# LC_FlowPCB_V6_3.net
KiCad netlist of a schematic drawn in Altium Designer
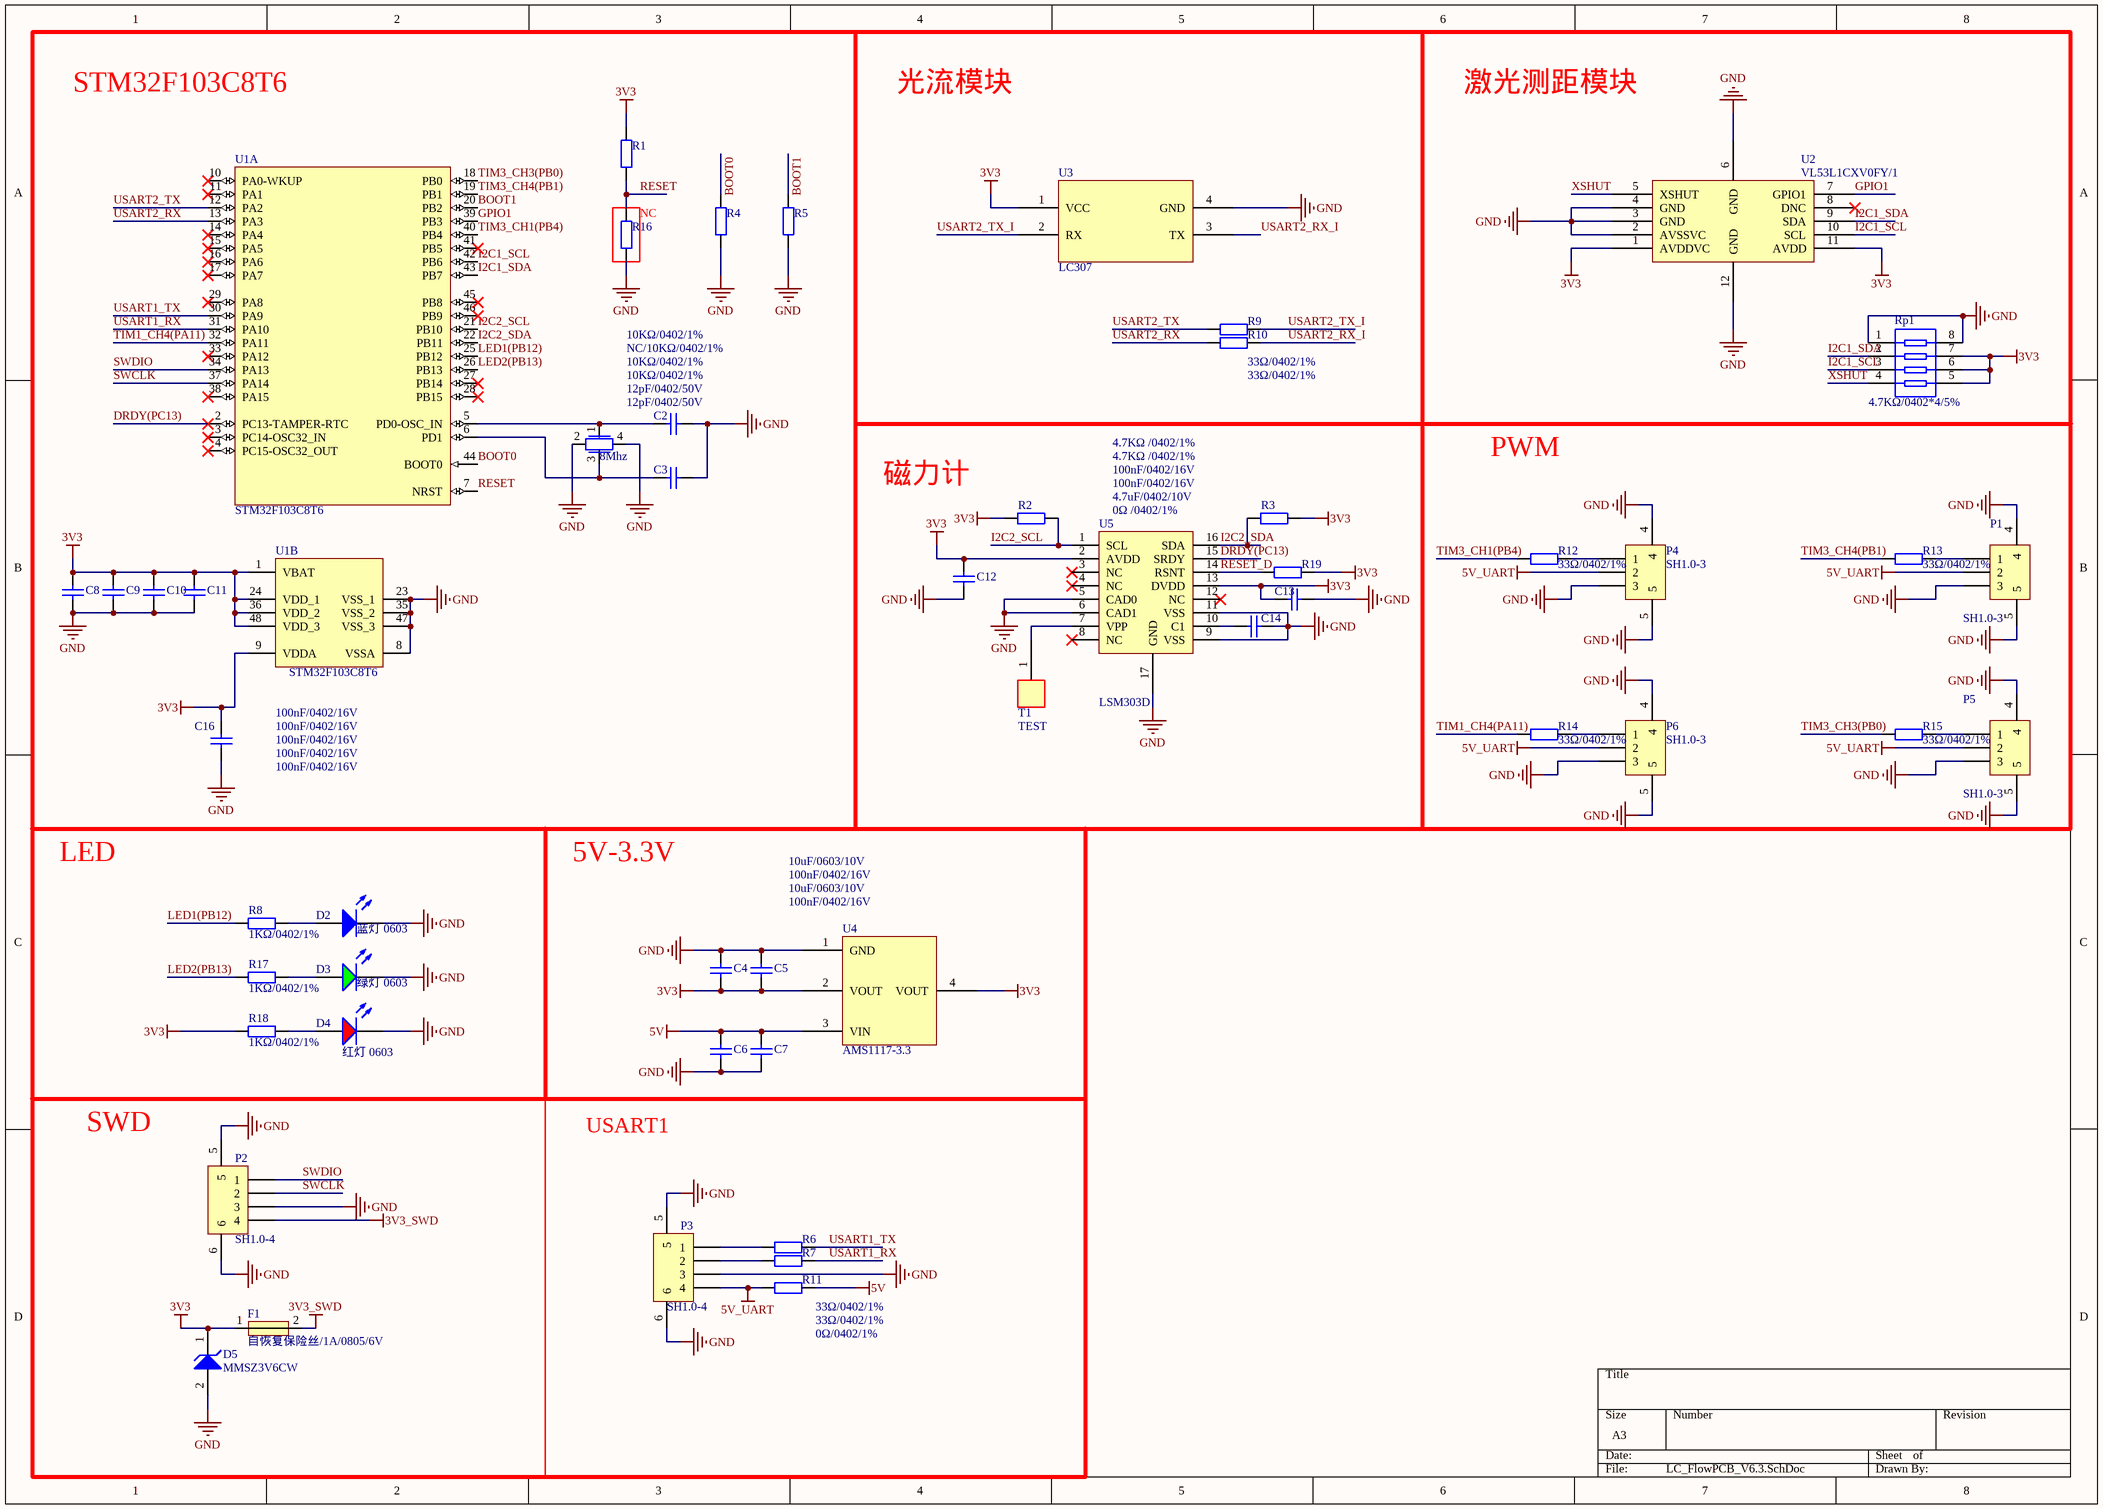
[diagram p0: LC_FlowPCB_V6.3.SchDoc]

(export (version "E")
  (design (tool "Eeschema 10.0.6"))
  (components
    (comp (ref "8Mhz")
      (value "无源贴片晶振")
      (footprint "RobotLab_Common_Used:SMD-3225_4P")
      (description "25M/3225")
      (libsource (lib "RobotLab_Common_Used") (part "XTAL_4"))
    )
    (comp (ref "C2")
      (value "12pF/0402/50V")
      (footprint "0402_C")
      (description "贴片电容")
      (libsource (lib "Miscellaneous Devices LC") (part "0402 22pF (220) 5% 50V"))
    )
    (comp (ref "C3")
      (value "12pF/0402/50V")
      (footprint "0402_C")
      (description "贴片电容")
      (libsource (lib "Miscellaneous Devices LC") (part "0402 22pF (220) 5% 50V"))
    )
    (comp (ref "C4")
      (value "10uF/0603/10V")
      (footprint "0603_C")
      (description "贴片电容")
      (libsource (lib "Miscellaneous Devices LC") (part "0603 10uF (106) 10% 10V"))
    )
    (comp (ref "C5")
      (value "100nF/0402/16V")
      (footprint "0402_C")
      (description "贴片电容")
      (libsource (lib "Miscellaneous Devices LC") (part "0402 100nF (104) 10% 16V"))
    )
    (comp (ref "C6")
      (value "10uF/0603/10V")
      (footprint "0603_C")
      (description "贴片电容")
      (libsource (lib "Miscellaneous Devices LC") (part "0603 10uF (106) 10% 10V"))
    )
    (comp (ref "C7")
      (value "100nF/0402/16V")
      (footprint "0402_C")
      (description "贴片电容")
      (libsource (lib "Miscellaneous Devices LC") (part "0402 100nF (104) 10% 16V"))
    )
    (comp (ref "C8")
      (value "100nF/0402/16V")
      (footprint "0402_C")
      (description "贴片电容")
      (libsource (lib "Miscellaneous Devices LC") (part "0402 100nF (104) 10% 16V"))
    )
    (comp (ref "C9")
      (value "100nF/0402/16V")
      (footprint "0402_C")
      (description "贴片电容")
      (libsource (lib "Miscellaneous Devices LC") (part "0402 100nF (104) 10% 16V"))
    )
    (comp (ref "C10")
      (value "100nF/0402/16V")
      (footprint "0402_C")
      (description "贴片电容")
      (libsource (lib "Miscellaneous Devices LC") (part "0402 100nF (104) 10% 16V"))
    )
    (comp (ref "C11")
      (value "100nF/0402/16V")
      (footprint "0402_C")
      (description "贴片电容")
      (libsource (lib "Miscellaneous Devices LC") (part "0402 100nF (104) 10% 16V"))
    )
    (comp (ref "C12")
      (value "100nF/0402/16V")
      (footprint "0402_C")
      (description "贴片电容")
      (libsource (lib "Miscellaneous Devices LC") (part "0402 100nF (104) 10% 16V"))
    )
    (comp (ref "C13")
      (value "100nF/0402/16V")
      (footprint "0402_C")
      (description "贴片电容")
      (libsource (lib "Miscellaneous Devices LC") (part "0402 100nF (104) 10% 16V"))
    )
    (comp (ref "C14")
      (value "4.7uF/0402/10V")
      (footprint "0402_C")
      (description "贴片电容")
      (libsource (lib "Miscellaneous Devices LC") (part "0402 4.7uF (475) 20% 10V"))
    )
    (comp (ref "C16")
      (value "100nF/0402/16V")
      (footprint "0402_C")
      (description "贴片电容")
      (libsource (lib "Miscellaneous Devices LC") (part "0402 100nF (104) 10% 16V"))
    )
    (comp (ref "D2")
      (value "蓝灯 0603")
      (footprint "0603_LED_S1")
      (description "发光二极管")
      (libsource (lib "Miscellaneous Devices LC") (part "0603 蓝灯"))
    )
    (comp (ref "D3")
      (value "绿灯 0603")
      (footprint "0603_LED_S1")
      (description "发光二极管")
      (libsource (lib "Miscellaneous Devices LC") (part "0603 绿灯"))
    )
    (comp (ref "D4")
      (value "红灯 0603")
      (footprint "0603_LED_S1")
      (description "发光二极管")
      (libsource (lib "Miscellaneous Devices LC") (part "0603 红灯"))
    )
    (comp (ref "D5")
      (value "MMSZ3V6CW")
      (footprint "SOD-123")
      (description "稳压二极管")
      (libsource (lib "LC_FlowPCB_V6.1") (part "LL-34 ZMM3V3"))
    )
    (comp (ref "F1")
      (value "自恢复保险丝/1A/0805/6V")
      (footprint "RobotLab_Common_Used:0805_R")
      (libsource (lib "RobotLab_Common_Used") (part "FUSE/0805"))
    )
    (comp (ref "P1")
      (value "SH1.0-3")
      (footprint "SH1.0-WS-3P")
      (description "Header, 3-Pin")
      (fields (field (name "PUBLISHER") "Altium Limited"))
      (libsource (lib "LC_FlowPCB_V6.1") (part "SH1.0-3"))
    )
    (comp (ref "P2")
      (value "SH1.0-4")
      (footprint "SH1.0-WS-4P")
      (description "Header, 4-Pin")
      (fields (field (name "PUBLISHER") "Altium Limited"))
      (libsource (lib "LC_FlowPCB_V6.1") (part "SH1.0-4"))
    )
    (comp (ref "P3")
      (value "SH1.0-4")
      (footprint "SH1.0-WS-4P")
      (description "Header, 4-Pin")
      (fields (field (name "PUBLISHER") "Altium Limited"))
      (libsource (lib "LC_FlowPCB_V6.1") (part "SH1.0-4"))
    )
    (comp (ref "P4")
      (value "SH1.0-3")
      (footprint "SH1.0-WS-3P")
      (description "Header, 3-Pin")
      (fields (field (name "PUBLISHER") "Altium Limited"))
      (libsource (lib "LC_FlowPCB_V6.1") (part "SH1.0-3"))
    )
    (comp (ref "P5")
      (value "SH1.0-3")
      (footprint "SH1.0-WS-3P")
      (description "Header, 3-Pin")
      (fields (field (name "PUBLISHER") "Altium Limited"))
      (libsource (lib "LC_FlowPCB_V6.1") (part "SH1.0-3"))
    )
    (comp (ref "P6")
      (value "SH1.0-3")
      (footprint "SH1.0-WS-3P")
      (description "Header, 3-Pin")
      (fields (field (name "PUBLISHER") "Altium Limited"))
      (libsource (lib "LC_FlowPCB_V6.1") (part "SH1.0-3"))
    )
    (comp (ref "R1")
      (value "10KΩ/0402/1%")
      (footprint "0402_R")
      (description "贴片电阻")
      (libsource (lib "Miscellaneous Devices LC") (part "0402 10KΩ (1002) 1%"))
    )
    (comp (ref "R2")
      (value "4.7KΩ /0402/1%")
      (footprint "0402_R")
      (description "贴片电阻")
      (libsource (lib "") (part "0402 4.7KΩ (4701) 1%_1"))
    )
    (comp (ref "R3")
      (value "4.7KΩ /0402/1%")
      (footprint "0402_R")
      (description "贴片电阻")
      (libsource (lib "Miscellaneous Devices LC") (part "0402 4.7KΩ (4701) 1%"))
    )
    (comp (ref "R4")
      (value "10KΩ/0402/1%")
      (footprint "0402_R")
      (description "贴片电阻")
      (libsource (lib "Miscellaneous Devices LC") (part "0402 10KΩ (1002) 1%"))
    )
    (comp (ref "R5")
      (value "10KΩ/0402/1%")
      (footprint "0402_R")
      (description "贴片电阻")
      (libsource (lib "Miscellaneous Devices LC") (part "0402 10KΩ (1002) 1%"))
    )
    (comp (ref "R6")
      (value "33Ω/0402/1%")
      (footprint "0402_R")
      (description "贴片电阻")
      (libsource (lib "") (part "0402 33Ω (33R0) 1%_1"))
    )
    (comp (ref "R7")
      (value "33Ω/0402/1%")
      (footprint "0402_R")
      (description "贴片电阻")
      (libsource (lib "") (part "0402 33Ω (33R0) 1%_1"))
    )
    (comp (ref "R8")
      (value "1KΩ/0402/1%")
      (footprint "0402_R")
      (description "贴片电阻")
      (libsource (lib "Miscellaneous Devices LC") (part "0402 1KΩ (1001) 1%"))
    )
    (comp (ref "R9")
      (value "33Ω/0402/1%")
      (footprint "0402_R")
      (description "贴片电阻")
      (libsource (lib "") (part "0402 33Ω (33R0) 1%_1"))
    )
    (comp (ref "R10")
      (value "33Ω/0402/1%")
      (footprint "0402_R")
      (description "贴片电阻")
      (libsource (lib "") (part "0402 33Ω (33R0) 1%_1"))
    )
    (comp (ref "R11")
      (value "0Ω/0402/1%")
      (footprint "0402_R")
      (description "贴片电阻")
      (libsource (lib "") (part "0402 33Ω (33R0) 1%_1"))
    )
    (comp (ref "R12")
      (value "33Ω/0402/1%")
      (footprint "0402_R")
      (description "贴片电阻")
      (libsource (lib "Miscellaneous Devices LC") (part "0402 33Ω (33R0) 1%"))
    )
    (comp (ref "R13")
      (value "33Ω/0402/1%")
      (footprint "0402_R")
      (description "贴片电阻")
      (libsource (lib "Miscellaneous Devices LC") (part "0402 33Ω (33R0) 1%"))
    )
    (comp (ref "R14")
      (value "33Ω/0402/1%")
      (footprint "0402_R")
      (description "贴片电阻")
      (libsource (lib "Miscellaneous Devices LC") (part "0402 33Ω (33R0) 1%"))
    )
    (comp (ref "R15")
      (value "33Ω/0402/1%")
      (footprint "0402_R")
      (description "贴片电阻")
      (libsource (lib "Miscellaneous Devices LC") (part "0402 33Ω (33R0) 1%"))
    )
    (comp (ref "R16")
      (value "NC/10KΩ/0402/1%")
      (footprint "0402_R")
      (description "贴片电阻")
      (libsource (lib "Miscellaneous Devices LC") (part "0402 10KΩ (1002) 1%"))
    )
    (comp (ref "R17")
      (value "1KΩ/0402/1%")
      (footprint "0402_R")
      (description "贴片电阻")
      (libsource (lib "Miscellaneous Devices LC") (part "0402 1KΩ (1001) 1%"))
    )
    (comp (ref "R18")
      (value "1KΩ/0402/1%")
      (footprint "0402_R")
      (description "贴片电阻")
      (libsource (lib "Miscellaneous Devices LC") (part "0402 1KΩ (1001) 1%"))
    )
    (comp (ref "R19")
      (value "0Ω /0402/1%")
      (footprint "0402_R")
      (description "贴片电阻")
      (libsource (lib "Miscellaneous Devices LC") (part "0402 4.7KΩ (4701) 1%"))
    )
    (comp (ref "Rp1")
      (value "4.7KΩ/0402*4/5%")
      (footprint "0402_Rx4")
      (description "贴片排阻")
      (libsource (lib "LC_FlowPCB_V6.1") (part "0402*4 1KΩ (102) 5%_1"))
    )
    (comp (ref "T1")
      (value "TEST")
      (footprint "测试点")
      (description "测试点")
      (libsource (lib "LC_FlowPCB_V6.1") (part "测试点"))
    )
    (comp (ref "U1")
      (value "STM32F103C8T6")
      (footprint "LQFP-48_7x7x05P")
      (description "ARM")
      (libsource (lib "Miscellaneous Devices LC") (part "STM32F103C8T6"))
    )
    (comp (ref "U2")
      (value "VL53L1CXV0FY/1")
      (footprint "LGA-12-2.5X4.9MM")
      (description "激光测距模块")
      (libsource (lib "LC_FlowPCB_V6.1") (part "VL53L1CXV0FY/1"))
    )
    (comp (ref "U3")
      (value "LC307")
      (footprint "LC307")
      (description "光流模块")
      (libsource (lib "LC_FlowPCB_V6.1") (part "LC307"))
    )
    (comp (ref "U4")
      (value "AMS1117-3.3")
      (footprint "SOT223")
      (description "LDO")
      (libsource (lib "LC_FlowPCB_V6.1") (part "AMS1117-3.3"))
    )
    (comp (ref "U5")
      (value "LSM303D")
      (footprint "QFN-16 (3×3)")
      (description "磁力计")
      (libsource (lib "LC_FlowPCB_V6.1") (part "IST8310"))
    )
  )
  (nets
    (net (code "1") (name "/BOOT0") (class "Default")
      (node (ref "R4") (pin "2") (pinfunction "2_2") (pintype "passive"))
      (node (ref "U1") (pin "44") (pinfunction "BOOT0_44") (pintype "input"))
    )
    (net (code "2") (name "/BOOT1") (class "Default")
      (node (ref "R5") (pin "2") (pinfunction "2_2") (pintype "passive"))
      (node (ref "U1") (pin "20") (pinfunction "PB2_20") (pintype "bidirectional"))
    )
    (net (code "3") (name "/DRDY(PC13)") (class "Default")
      (node (ref "U1") (pin "2") (pinfunction "PC13-TAMPER-RTC_2") (pintype "bidirectional"))
      (node (ref "U5") (pin "15") (pinfunction "SRDY_15") (pintype "passive"))
    )
    (net (code "4") (name "/GPIO1") (class "Default")
      (node (ref "U1") (pin "39") (pinfunction "PB3_39") (pintype "bidirectional"))
      (node (ref "U2") (pin "7") (pinfunction "GPIO1_7") (pintype "passive"))
    )
    (net (code "5") (name "/I2C1_SCL") (class "Default")
      (node (ref "Rp1") (pin "3") (pinfunction "3_3") (pintype "passive"))
      (node (ref "U1") (pin "42") (pinfunction "PB6_42") (pintype "bidirectional"))
      (node (ref "U2") (pin "10") (pinfunction "SCL_10") (pintype "passive"))
    )
    (net (code "6") (name "/I2C1_SDA") (class "Default")
      (node (ref "Rp1") (pin "2") (pinfunction "2_2") (pintype "passive"))
      (node (ref "U1") (pin "43") (pinfunction "PB7_43") (pintype "bidirectional"))
      (node (ref "U2") (pin "9") (pinfunction "SDA_9") (pintype "passive"))
    )
    (net (code "7") (name "/I2C2_SCL") (class "Default")
      (node (ref "R2") (pin "1") (pinfunction "1_1") (pintype "passive"))
      (node (ref "U1") (pin "21") (pinfunction "PB10_21") (pintype "bidirectional"))
      (node (ref "U5") (pin "1") (pinfunction "SCL_1") (pintype "passive"))
    )
    (net (code "8") (name "/I2C2_SDA") (class "Default")
      (node (ref "R3") (pin "1") (pinfunction "1_1") (pintype "passive"))
      (node (ref "U1") (pin "22") (pinfunction "PB11_22") (pintype "bidirectional"))
      (node (ref "U5") (pin "16") (pinfunction "SDA_16") (pintype "passive"))
    )
    (net (code "9") (name "/LED1(PB12)") (class "Default")
      (node (ref "R8") (pin "1") (pinfunction "1_1") (pintype "passive"))
      (node (ref "U1") (pin "25") (pinfunction "PB12_25") (pintype "bidirectional"))
    )
    (net (code "10") (name "/LED2(PB13)") (class "Default")
      (node (ref "R17") (pin "1") (pinfunction "1_1") (pintype "passive"))
      (node (ref "U1") (pin "26") (pinfunction "PB13_26") (pintype "bidirectional"))
    )
    (net (code "11") (name "/RESET") (class "Default")
      (node (ref "R1") (pin "1") (pinfunction "1_1") (pintype "passive"))
      (node (ref "R16") (pin "2") (pinfunction "2_2") (pintype "passive"))
      (node (ref "U1") (pin "7") (pinfunction "NRST_7") (pintype "bidirectional"))
    )
    (net (code "12") (name "/RESET_D") (class "Default")
      (node (ref "R19") (pin "1") (pinfunction "1_1") (pintype "passive"))
      (node (ref "U5") (pin "14") (pinfunction "RSNT_14") (pintype "passive"))
    )
    (net (code "13") (name "/SWCLK") (class "Default")
      (node (ref "P2") (pin "2") (pinfunction "2_2") (pintype "passive"))
      (node (ref "U1") (pin "37") (pinfunction "PA14_37") (pintype "bidirectional"))
    )
    (net (code "14") (name "/SWDIO") (class "Default")
      (node (ref "P2") (pin "1") (pinfunction "1_1") (pintype "passive"))
      (node (ref "U1") (pin "34") (pinfunction "PA13_34") (pintype "bidirectional"))
    )
    (net (code "15") (name "/TIM1_CH4(PA11)") (class "Default")
      (node (ref "R14") (pin "2") (pinfunction "2_2") (pintype "passive"))
      (node (ref "U1") (pin "32") (pinfunction "PA11_32") (pintype "bidirectional"))
    )
    (net (code "16") (name "/TIM3_CH1(PB4)") (class "Default")
      (node (ref "R12") (pin "2") (pinfunction "2_2") (pintype "passive"))
      (node (ref "U1") (pin "40") (pinfunction "PB4_40") (pintype "bidirectional"))
    )
    (net (code "17") (name "/TIM3_CH3(PB0)") (class "Default")
      (node (ref "R15") (pin "2") (pinfunction "2_2") (pintype "passive"))
      (node (ref "U1") (pin "18") (pinfunction "PB0_18") (pintype "bidirectional"))
    )
    (net (code "18") (name "/TIM3_CH4(PB1)") (class "Default")
      (node (ref "R13") (pin "2") (pinfunction "2_2") (pintype "passive"))
      (node (ref "U1") (pin "19") (pinfunction "PB1_19") (pintype "bidirectional"))
    )
    (net (code "19") (name "/USART1_RX") (class "Default")
      (node (ref "R7") (pin "2") (pinfunction "2_2") (pintype "passive"))
      (node (ref "U1") (pin "31") (pinfunction "PA10_31") (pintype "bidirectional"))
    )
    (net (code "20") (name "/USART1_TX") (class "Default")
      (node (ref "R6") (pin "2") (pinfunction "2_2") (pintype "passive"))
      (node (ref "U1") (pin "30") (pinfunction "PA9_30") (pintype "bidirectional"))
    )
    (net (code "21") (name "/USART2_RX") (class "Default")
      (node (ref "R10") (pin "1") (pinfunction "1_1") (pintype "passive"))
      (node (ref "U1") (pin "13") (pinfunction "PA3_13") (pintype "bidirectional"))
    )
    (net (code "22") (name "/USART2_RX_I") (class "Default")
      (node (ref "R10") (pin "2") (pinfunction "2_2") (pintype "passive"))
      (node (ref "U3") (pin "3") (pinfunction "TX_3") (pintype "passive"))
    )
    (net (code "23") (name "/USART2_TX") (class "Default")
      (node (ref "R9") (pin "1") (pinfunction "1_1") (pintype "passive"))
      (node (ref "U1") (pin "12") (pinfunction "PA2_12") (pintype "bidirectional"))
    )
    (net (code "24") (name "/USART2_TX_I") (class "Default")
      (node (ref "R9") (pin "2") (pinfunction "2_2") (pintype "passive"))
      (node (ref "U3") (pin "2") (pinfunction "RX_2") (pintype "passive"))
    )
    (net (code "25") (name "/XSHUT") (class "Default")
      (node (ref "Rp1") (pin "4") (pinfunction "4_4") (pintype "passive"))
      (node (ref "U2") (pin "5") (pinfunction "XSHUT_5") (pintype "passive"))
    )
    (net (code "26") (name "3V3") (class "Default")
      (node (ref "C10") (pin "2") (pinfunction "2_2") (pintype "passive"))
      (node (ref "C11") (pin "2") (pinfunction "2_2") (pintype "passive"))
      (node (ref "C12") (pin "2") (pinfunction "2_2") (pintype "passive"))
      (node (ref "C13") (pin "2") (pinfunction "2_2") (pintype "passive"))
      (node (ref "C16") (pin "2") (pinfunction "2_2") (pintype "passive"))
      (node (ref "C4") (pin "1") (pinfunction "1_1") (pintype "passive"))
      (node (ref "C5") (pin "1") (pinfunction "1_1") (pintype "passive"))
      (node (ref "C8") (pin "2") (pinfunction "2_2") (pintype "passive"))
      (node (ref "C9") (pin "2") (pinfunction "2_2") (pintype "passive"))
      (node (ref "D5") (pin "1") (pinfunction "K_1") (pintype "passive"))
      (node (ref "F1") (pin "1") (pintype "passive"))
      (node (ref "R1") (pin "2") (pinfunction "2_2") (pintype "passive"))
      (node (ref "R18") (pin "1") (pinfunction "1_1") (pintype "passive"))
      (node (ref "R19") (pin "2") (pinfunction "2_2") (pintype "passive"))
      (node (ref "R2") (pin "2") (pinfunction "2_2") (pintype "passive"))
      (node (ref "R3") (pin "2") (pinfunction "2_2") (pintype "passive"))
      (node (ref "Rp1") (pin "5") (pinfunction "5_5") (pintype "passive"))
      (node (ref "Rp1") (pin "6") (pinfunction "6_6") (pintype "passive"))
      (node (ref "Rp1") (pin "7") (pinfunction "7_7") (pintype "passive"))
      (node (ref "U1") (pin "1") (pinfunction "VBAT_1") (pintype "power_in"))
      (node (ref "U1") (pin "24") (pinfunction "VDD_1_24") (pintype "power_in"))
      (node (ref "U1") (pin "36") (pinfunction "VDD_2_36") (pintype "power_in"))
      (node (ref "U1") (pin "48") (pinfunction "VDD_3_48") (pintype "power_in"))
      (node (ref "U1") (pin "9") (pinfunction "VDDA_9") (pintype "power_in"))
      (node (ref "U2") (pin "1") (pinfunction "AVDDVC_1") (pintype "passive"))
      (node (ref "U2") (pin "11") (pinfunction "AVDD_11") (pintype "passive"))
      (node (ref "U3") (pin "1") (pinfunction "VCC_1") (pintype "passive"))
      (node (ref "U4") (pin "2") (pinfunction "VOUT_2") (pintype "passive"))
      (node (ref "U4") (pin "4") (pinfunction "VOUT_4") (pintype "passive"))
      (node (ref "U5") (pin "13") (pinfunction "DVDD_13") (pintype "passive"))
      (node (ref "U5") (pin "2") (pinfunction "AVDD_2") (pintype "passive"))
    )
    (net (code "27") (name "3V3_SWD") (class "Default")
      (node (ref "F1") (pin "2") (pintype "passive"))
      (node (ref "P2") (pin "4") (pinfunction "4_4") (pintype "passive"))
    )
    (net (code "28") (name "5V") (class "Default")
      (node (ref "C6") (pin "2") (pinfunction "2_2") (pintype "passive"))
      (node (ref "C7") (pin "2") (pinfunction "2_2") (pintype "passive"))
      (node (ref "R11") (pin "2") (pinfunction "2_2") (pintype "passive"))
      (node (ref "U4") (pin "3") (pinfunction "VIN_3") (pintype "passive"))
    )
    (net (code "29") (name "5V_UART") (class "Default")
      (node (ref "P1") (pin "2") (pinfunction "2_2") (pintype "passive"))
      (node (ref "P3") (pin "4") (pinfunction "4_4") (pintype "passive"))
      (node (ref "P4") (pin "2") (pinfunction "2_2") (pintype "passive"))
      (node (ref "P5") (pin "2") (pinfunction "2_2") (pintype "passive"))
      (node (ref "P6") (pin "2") (pinfunction "2_2") (pintype "passive"))
      (node (ref "R11") (pin "1") (pinfunction "1_1") (pintype "passive"))
    )
    (net (code "30") (name "GND") (class "Default")
      (node (ref "8Mhz") (pin "2") (pinfunction "GND_2") (pintype "passive"))
      (node (ref "8Mhz") (pin "4") (pinfunction "GND_4") (pintype "passive"))
      (node (ref "C10") (pin "1") (pinfunction "1_1") (pintype "passive"))
      (node (ref "C11") (pin "1") (pinfunction "1_1") (pintype "passive"))
      (node (ref "C12") (pin "1") (pinfunction "1_1") (pintype "passive"))
      (node (ref "C13") (pin "1") (pinfunction "1_1") (pintype "passive"))
      (node (ref "C14") (pin "2") (pinfunction "2_2") (pintype "passive"))
      (node (ref "C16") (pin "1") (pinfunction "1_1") (pintype "passive"))
      (node (ref "C2") (pin "2") (pinfunction "2_2") (pintype "passive"))
      (node (ref "C3") (pin "2") (pinfunction "2_2") (pintype "passive"))
      (node (ref "C4") (pin "2") (pinfunction "2_2") (pintype "passive"))
      (node (ref "C5") (pin "2") (pinfunction "2_2") (pintype "passive"))
      (node (ref "C6") (pin "1") (pinfunction "1_1") (pintype "passive"))
      (node (ref "C7") (pin "1") (pinfunction "1_1") (pintype "passive"))
      (node (ref "C8") (pin "1") (pinfunction "1_1") (pintype "passive"))
      (node (ref "C9") (pin "1") (pinfunction "1_1") (pintype "passive"))
      (node (ref "D2") (pin "K") (pinfunction "K_K") (pintype "passive"))
      (node (ref "D3") (pin "K") (pinfunction "K_K") (pintype "passive"))
      (node (ref "D4") (pin "K") (pinfunction "K_K") (pintype "passive"))
      (node (ref "D5") (pin "2") (pinfunction "A_2") (pintype "passive"))
      (node (ref "P1") (pin "3") (pinfunction "3_3") (pintype "passive"))
      (node (ref "P1") (pin "4") (pinfunction "4_4") (pintype "passive"))
      (node (ref "P1") (pin "5") (pinfunction "5_5") (pintype "passive"))
      (node (ref "P2") (pin "3") (pinfunction "3_3") (pintype "passive"))
      (node (ref "P2") (pin "5") (pinfunction "5_5") (pintype "passive"))
      (node (ref "P2") (pin "6") (pinfunction "6_6") (pintype "passive"))
      (node (ref "P3") (pin "3") (pinfunction "3_3") (pintype "passive"))
      (node (ref "P3") (pin "5") (pinfunction "5_5") (pintype "passive"))
      (node (ref "P3") (pin "6") (pinfunction "6_6") (pintype "passive"))
      (node (ref "P4") (pin "3") (pinfunction "3_3") (pintype "passive"))
      (node (ref "P4") (pin "4") (pinfunction "4_4") (pintype "passive"))
      (node (ref "P4") (pin "5") (pinfunction "5_5") (pintype "passive"))
      (node (ref "P5") (pin "3") (pinfunction "3_3") (pintype "passive"))
      (node (ref "P5") (pin "4") (pinfunction "4_4") (pintype "passive"))
      (node (ref "P5") (pin "5") (pinfunction "5_5") (pintype "passive"))
      (node (ref "P6") (pin "3") (pinfunction "3_3") (pintype "passive"))
      (node (ref "P6") (pin "4") (pinfunction "4_4") (pintype "passive"))
      (node (ref "P6") (pin "5") (pinfunction "5_5") (pintype "passive"))
      (node (ref "R16") (pin "1") (pinfunction "1_1") (pintype "passive"))
      (node (ref "R4") (pin "1") (pinfunction "1_1") (pintype "passive"))
      (node (ref "R5") (pin "1") (pinfunction "1_1") (pintype "passive"))
      (node (ref "Rp1") (pin "1") (pinfunction "1_1") (pintype "passive"))
      (node (ref "Rp1") (pin "8") (pinfunction "8_8") (pintype "passive"))
      (node (ref "U1") (pin "23") (pinfunction "VSS_1_23") (pintype "power_in"))
      (node (ref "U1") (pin "35") (pinfunction "VSS_2_35") (pintype "power_in"))
      (node (ref "U1") (pin "47") (pinfunction "VSS_3_47") (pintype "power_in"))
      (node (ref "U1") (pin "8") (pinfunction "VSSA_8") (pintype "power_in"))
      (node (ref "U2") (pin "12") (pinfunction "GND_12") (pintype "passive"))
      (node (ref "U2") (pin "2") (pinfunction "AVSSVC_2") (pintype "passive"))
      (node (ref "U2") (pin "3") (pinfunction "GND_3") (pintype "passive"))
      (node (ref "U2") (pin "4") (pinfunction "GND_4") (pintype "passive"))
      (node (ref "U2") (pin "6") (pinfunction "GND_6") (pintype "passive"))
      (node (ref "U3") (pin "4") (pinfunction "GND_4") (pintype "passive"))
      (node (ref "U4") (pin "1") (pinfunction "GND_1") (pintype "passive"))
      (node (ref "U5") (pin "11") (pinfunction "VSS_11") (pintype "passive"))
      (node (ref "U5") (pin "17") (pinfunction "GND_17") (pintype "passive"))
      (node (ref "U5") (pin "5") (pinfunction "CAD0_5") (pintype "passive"))
      (node (ref "U5") (pin "6") (pinfunction "CAD1_6") (pintype "passive"))
      (node (ref "U5") (pin "9") (pinfunction "VSS_9") (pintype "passive"))
    )
    (net (code "31") (name "Net-(D2-PadA)") (class "Default")
      (node (ref "D2") (pin "A") (pinfunction "A_A") (pintype "passive"))
      (node (ref "R8") (pin "2") (pinfunction "2_2") (pintype "passive"))
    )
    (net (code "32") (name "Net-(D3-PadA)") (class "Default")
      (node (ref "D3") (pin "A") (pinfunction "A_A") (pintype "passive"))
      (node (ref "R17") (pin "2") (pinfunction "2_2") (pintype "passive"))
    )
    (net (code "33") (name "Net-(D4-PadA)") (class "Default")
      (node (ref "D4") (pin "A") (pinfunction "A_A") (pintype "passive"))
      (node (ref "R18") (pin "2") (pinfunction "2_2") (pintype "passive"))
    )
    (net (code "34") (name "Net-(P1-Pad1)") (class "Default")
      (node (ref "P1") (pin "1") (pinfunction "1_1") (pintype "passive"))
      (node (ref "R13") (pin "1") (pinfunction "1_1") (pintype "passive"))
    )
    (net (code "35") (name "Net-(P3-Pad1)") (class "Default")
      (node (ref "P3") (pin "1") (pinfunction "1_1") (pintype "passive"))
      (node (ref "R6") (pin "1") (pinfunction "1_1") (pintype "passive"))
    )
    (net (code "36") (name "Net-(P3-Pad2)") (class "Default")
      (node (ref "P3") (pin "2") (pinfunction "2_2") (pintype "passive"))
      (node (ref "R7") (pin "1") (pinfunction "1_1") (pintype "passive"))
    )
    (net (code "37") (name "Net-(P4-Pad1)") (class "Default")
      (node (ref "P4") (pin "1") (pinfunction "1_1") (pintype "passive"))
      (node (ref "R12") (pin "1") (pinfunction "1_1") (pintype "passive"))
    )
    (net (code "38") (name "Net-(P5-Pad1)") (class "Default")
      (node (ref "P5") (pin "1") (pinfunction "1_1") (pintype "passive"))
      (node (ref "R15") (pin "1") (pinfunction "1_1") (pintype "passive"))
    )
    (net (code "39") (name "Net-(P6-Pad1)") (class "Default")
      (node (ref "P6") (pin "1") (pinfunction "1_1") (pintype "passive"))
      (node (ref "R14") (pin "1") (pinfunction "1_1") (pintype "passive"))
    )
    (net (code "40") (name "Net-(T1-VIN)") (class "Default")
      (node (ref "T1") (pin "1") (pinfunction "VIN_1") (pintype "passive"))
      (node (ref "U5") (pin "7") (pinfunction "VPP_7") (pintype "passive"))
    )
    (net (code "41") (name "Net-(U1A-PD0-OSC_IN)") (class "Default")
      (node (ref "8Mhz") (pin "1") (pinfunction "OUT_1") (pintype "passive"))
      (node (ref "C2") (pin "1") (pinfunction "1_1") (pintype "passive"))
      (node (ref "U1") (pin "5") (pinfunction "PD0-OSC_IN_5") (pintype "bidirectional"))
    )
    (net (code "42") (name "Net-(U1A-PD1)") (class "Default")
      (node (ref "8Mhz") (pin "3") (pinfunction "OUT_3") (pintype "passive"))
      (node (ref "C3") (pin "1") (pinfunction "1_1") (pintype "passive"))
      (node (ref "U1") (pin "6") (pinfunction "PD1_6") (pintype "bidirectional"))
    )
    (net (code "43") (name "Net-(U5-C1)") (class "Default")
      (node (ref "C14") (pin "1") (pinfunction "1_1") (pintype "passive"))
      (node (ref "U5") (pin "10") (pinfunction "C1_10") (pintype "passive"))
    )
    (net (code "44") (name "unconnected-(U1A-PA0-WKUP-Pad10)") (class "Default")
      (node (ref "U1") (pin "10") (pinfunction "PA0-WKUP_10") (pintype "bidirectional+no_connect"))
    )
    (net (code "45") (name "unconnected-(U1A-PA1-Pad11)") (class "Default")
      (node (ref "U1") (pin "11") (pinfunction "PA1_11") (pintype "bidirectional+no_connect"))
    )
    (net (code "46") (name "unconnected-(U1A-PA4-Pad14)") (class "Default")
      (node (ref "U1") (pin "14") (pinfunction "PA4_14") (pintype "bidirectional+no_connect"))
    )
    (net (code "47") (name "unconnected-(U1A-PA5-Pad15)") (class "Default")
      (node (ref "U1") (pin "15") (pinfunction "PA5_15") (pintype "bidirectional+no_connect"))
    )
    (net (code "48") (name "unconnected-(U1A-PA6-Pad16)") (class "Default")
      (node (ref "U1") (pin "16") (pinfunction "PA6_16") (pintype "bidirectional+no_connect"))
    )
    (net (code "49") (name "unconnected-(U1A-PA7-Pad17)") (class "Default")
      (node (ref "U1") (pin "17") (pinfunction "PA7_17") (pintype "bidirectional+no_connect"))
    )
    (net (code "50") (name "unconnected-(U1A-PA8-Pad29)") (class "Default")
      (node (ref "U1") (pin "29") (pinfunction "PA8_29") (pintype "bidirectional+no_connect"))
    )
    (net (code "51") (name "unconnected-(U1A-PA12-Pad33)") (class "Default")
      (node (ref "U1") (pin "33") (pinfunction "PA12_33") (pintype "bidirectional+no_connect"))
    )
    (net (code "52") (name "unconnected-(U1A-PA15-Pad38)") (class "Default")
      (node (ref "U1") (pin "38") (pinfunction "PA15_38") (pintype "bidirectional+no_connect"))
    )
    (net (code "53") (name "unconnected-(U1A-PB5-Pad41)") (class "Default")
      (node (ref "U1") (pin "41") (pinfunction "PB5_41") (pintype "bidirectional+no_connect"))
    )
    (net (code "54") (name "unconnected-(U1A-PB8-Pad45)") (class "Default")
      (node (ref "U1") (pin "45") (pinfunction "PB8_45") (pintype "bidirectional+no_connect"))
    )
    (net (code "55") (name "unconnected-(U1A-PB9-Pad46)") (class "Default")
      (node (ref "U1") (pin "46") (pinfunction "PB9_46") (pintype "bidirectional+no_connect"))
    )
    (net (code "56") (name "unconnected-(U1A-PB14-Pad27)") (class "Default")
      (node (ref "U1") (pin "27") (pinfunction "PB14_27") (pintype "bidirectional+no_connect"))
    )
    (net (code "57") (name "unconnected-(U1A-PB15-Pad28)") (class "Default")
      (node (ref "U1") (pin "28") (pinfunction "PB15_28") (pintype "bidirectional+no_connect"))
    )
    (net (code "58") (name "unconnected-(U1A-PC14-OSC32_IN-Pad3)") (class "Default")
      (node (ref "U1") (pin "3") (pinfunction "PC14-OSC32_IN_3") (pintype "bidirectional+no_connect"))
    )
    (net (code "59") (name "unconnected-(U1A-PC15-OSC32_OUT-Pad4)") (class "Default")
      (node (ref "U1") (pin "4") (pinfunction "PC15-OSC32_OUT_4") (pintype "bidirectional+no_connect"))
    )
    (net (code "60") (name "unconnected-(U2-DNC-Pad8)") (class "Default")
      (node (ref "U2") (pin "8") (pinfunction "DNC_8") (pintype "passive+no_connect"))
    )
    (net (code "61") (name "unconnected-(U5-NC-Pad3)") (class "Default")
      (node (ref "U5") (pin "3") (pinfunction "NC_3") (pintype "passive+no_connect"))
    )
    (net (code "62") (name "unconnected-(U5-NC-Pad4)") (class "Default")
      (node (ref "U5") (pin "4") (pinfunction "NC_4") (pintype "passive+no_connect"))
    )
    (net (code "63") (name "unconnected-(U5-NC-Pad8)") (class "Default")
      (node (ref "U5") (pin "8") (pinfunction "NC_8") (pintype "passive+no_connect"))
    )
    (net (code "64") (name "unconnected-(U5-NC-Pad12)") (class "Default")
      (node (ref "U5") (pin "12") (pinfunction "NC_12") (pintype "passive+no_connect"))
    )
  )
)
